# REVERSE_PROTECTION.net
KiCad netlist of a schematic drawn in Altium Designer
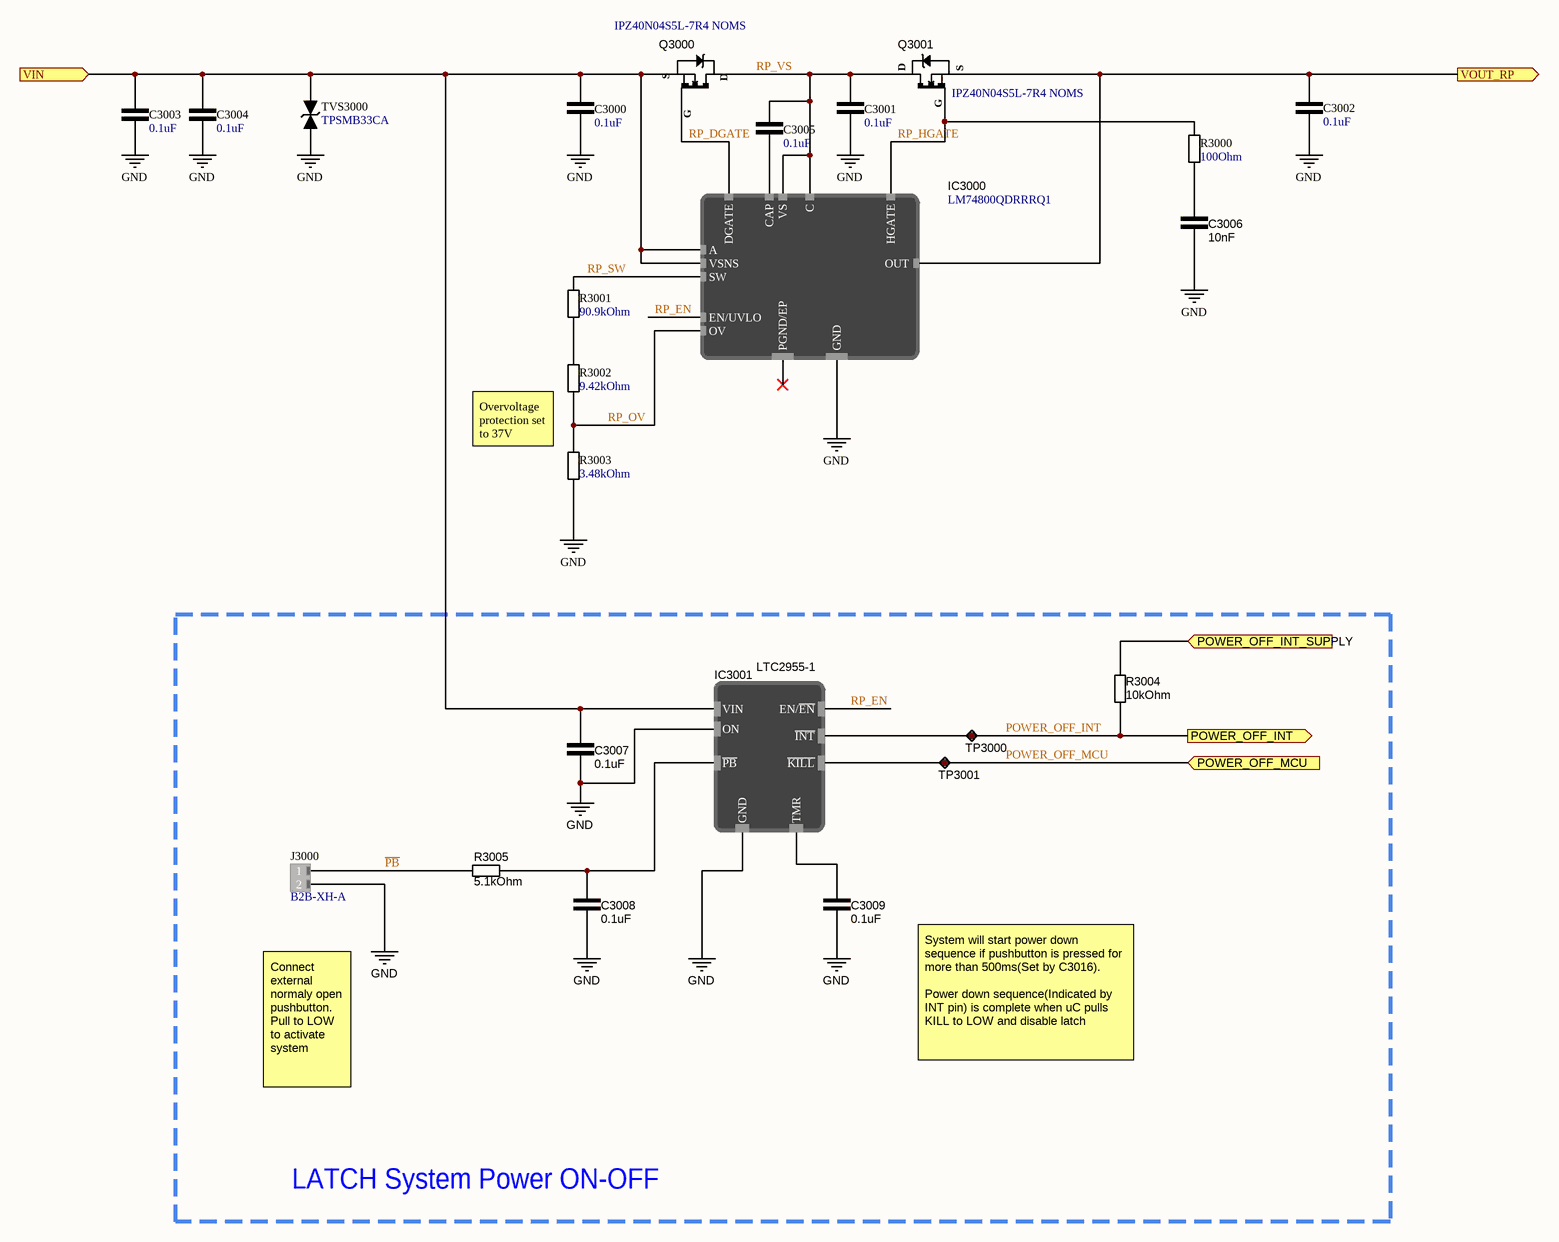
[diagram p0: REVERSE_PROTECTION.SchDoc]

(export (version "E")
  (design (tool "Eeschema 10.0.6"))
  (components
    (comp (ref "C3000")
      (value "0.1uF")
      (footprint "CAP_0603")
      (description "0.1 µF ±10% 50V Ceramic Capacitor X7R 0603 (1608 Metric)")
      (fields (field (name "DIGIKEY PART NUMBER") "1276-1000-1-ND"))
      (libsource (lib "CapacitorsIntegrated") (part "C000018"))
    )
    (comp (ref "C3001")
      (value "0.1uF")
      (footprint "CAP_0603")
      (description "0.1 µF ±10% 50V Ceramic Capacitor X7R 0603 (1608 Metric)")
      (fields (field (name "DIGIKEY PART NUMBER") "1276-1000-1-ND"))
      (libsource (lib "CapacitorsIntegrated") (part "C000018"))
    )
    (comp (ref "C3002")
      (value "0.1uF")
      (footprint "CAP_0603")
      (description "0.1 µF ±10% 50V Ceramic Capacitor X7R 0603 (1608 Metric)")
      (fields (field (name "DIGIKEY PART NUMBER") "1276-1000-1-ND"))
      (libsource (lib "CapacitorsIntegrated") (part "C000018"))
    )
    (comp (ref "C3003")
      (value "0.1uF")
      (footprint "CAP_0603")
      (description "0.1 µF ±10% 50V Ceramic Capacitor X7R 0603 (1608 Metric)")
      (fields (field (name "DIGIKEY PART NUMBER") "1276-1000-1-ND"))
      (libsource (lib "CapacitorsIntegrated") (part "C000018"))
    )
    (comp (ref "C3004")
      (value "0.1uF")
      (footprint "CAP_0603")
      (description "0.1 µF ±10% 50V Ceramic Capacitor X7R 0603 (1608 Metric)")
      (fields (field (name "DIGIKEY PART NUMBER") "1276-1000-1-ND"))
      (libsource (lib "CapacitorsIntegrated") (part "C000018"))
    )
    (comp (ref "C3005")
      (value "0.1uF")
      (footprint "CAP_0603")
      (description "0.1 µF ±10% 50V Ceramic Capacitor X7R 0603 (1608 Metric)")
      (fields (field (name "DIGIKEY PART NUMBER") "1276-1000-1-ND"))
      (libsource (lib "CapacitorsIntegrated") (part "C000018"))
    )
    (comp (ref "C3006")
      (value "10nF")
      (footprint "CAP_0603")
      (description "10000 pF ±10% 50V Ceramic Capacitor X7R 0603 (1608 Metric)")
      (fields (field (name "DIGIKEY PART NUMBER") "399-C0603C103K5RACTUCT-ND"))
      (libsource (lib "CapacitorsIntegrated") (part "C000034"))
    )
    (comp (ref "C3007")
      (value "0.1uF")
      (footprint "CAP_0603")
      (description "0.1 µF ±10% 50V Ceramic Capacitor X7R 0603 (1608 Metric)")
      (fields (field (name "DIGIKEY PART NUMBER") "1276-1000-1-ND"))
      (libsource (lib "CapacitorsIntegrated") (part "C000018"))
    )
    (comp (ref "C3008")
      (value "0.1uF")
      (footprint "CAP_0603")
      (description "0.1 µF ±10% 50V Ceramic Capacitor X7R 0603 (1608 Metric)")
      (fields (field (name "DIGIKEY PART NUMBER") "1276-1000-1-ND"))
      (libsource (lib "CapacitorsIntegrated") (part "C000018"))
    )
    (comp (ref "C3009")
      (value "0.1uF")
      (footprint "CAP_0603")
      (description "0.1 µF ±10% 50V Ceramic Capacitor X7R 0603 (1608 Metric)")
      (fields (field (name "DIGIKEY PART NUMBER") "1276-1000-1-ND"))
      (libsource (lib "CapacitorsIntegrated") (part "C000018"))
    )
    (comp (ref "IC3000")
      (value "LM74800QDRRRQ1")
      (footprint "SON50P300X80_HS-13N")
      (description "OR Controller N+1 ORing Controller N-Channel 1:1 12-WSON (3x3)")
      (fields
        (field (name "DIGIKEY PART NUMBER") "296-LM74800QDRRRQ1CT-ND")
        (field (name "MOUSER PART NUMBER") "595-LM74800QDRRRQ1")
      )
      (libsource (lib "IntegratedCircuits") (part "LM74800QDRRRQ1"))
    )
    (comp (ref "IC3001")
      (value "LTC2955-1")
      (footprint "TSOP65P280X100-8N")
      (description "Power Supply Controller Push Button, On/Off Controller TSOT-23-8")
      (fields
        (field (name "DIGIKEY PART NUMBER") "505-LTC2955CTS8-1#TRMPBFCT-ND")
        (field (name "MOUSER PART NUMBER") "584-C2955CTS8-1TMPF")
      )
      (libsource (lib "IntegratedCircuits") (part "LTC2955-1"))
    )
    (comp (ref "J3000")
      (value "B2B-XH-A")
      (footprint "JST_XH_2POS")
      (description "Connector Header Through Hole 2 position 0.098\" (2.50mm)")
      (fields (field (name "DIGIKEY PART NUMBER") "455-B2B-XH-A-ND"))
      (libsource (lib "ElectroMechanical") (part "00000013"))
    )
    (comp (ref "Q3000")
      (value "IPZ40N04S5L-7R4 NOMS")
      (footprint "PG-TSDSON-8-32")
      (description "N-Channel 40 V 40A (Tc) 34W (Tc) Surface Mount PG-TSDSON-8")
      (fields
        (field (name "DIGIKEY PART NUMBER") "IPZ40N04S5L7R4ATMA1CT-ND")
        (field (name "MOUSER PART NUMBER") "726-IPZ40N04S5L7R4AT")
      )
      (libsource (lib "") (part "00000007_1"))
    )
    (comp (ref "Q3001")
      (value "IPZ40N04S5L-7R4 NOMS")
      (footprint "PG-TSDSON-8-32")
      (description "N-Channel 40 V 40A (Tc) 34W (Tc) Surface Mount PG-TSDSON-8")
      (fields
        (field (name "DIGIKEY PART NUMBER") "IPZ40N04S5L7R4ATMA1CT-ND")
        (field (name "MOUSER PART NUMBER") "726-IPZ40N04S5L7R4AT")
      )
      (libsource (lib "Miscellaneous_Lib1") (part "00000007"))
    )
    (comp (ref "R3000")
      (value "100Ohm")
      (footprint "RES_0603")
      (description "100 Ohms ±1% 0.1W, 1/10W Chip Resistor 0603 (1608 Metric) Moisture Resistant Thick Film")
      (fields (field (name "DIGIKEY PART NUMBER") "311-100HRCT-ND"))
      (libsource (lib "ResistorsIntegrated") (part "R000030"))
    )
    (comp (ref "R3001")
      (value "90.9kOhm")
      (footprint "RES_0603")
      (description "90.9 kOhms ±1% 0.1W, 1/10W Chip Resistor 0603 (1608 Metric) Automotive AEC-Q200 Thick Film")
      (fields (field (name "DIGIKEY PART NUMBER") "P90.9KHCT-ND"))
      (libsource (lib "ResistorsIntegrated") (part "R000027"))
    )
    (comp (ref "R3002")
      (value "9.42kOhm")
      (footprint "RES_0603")
      (fields (field (name "DIGIKEY PART NUMBER") "2019-RN73H1JTTD9421F25CT-ND"))
      (libsource (lib "ResistorsIntegrated") (part "R000028"))
    )
    (comp (ref "R3003")
      (value "3.48kOhm")
      (footprint "RES_0603")
      (description "3.48 kOhms ±1% 0.1W, 1/10W Chip Resistor 0603 (1608 Metric) Automotive AEC-Q200 Thick Film")
      (fields (field (name "DIGIKEY PART NUMBER") "RMCF0603FT3K48CT-ND"))
      (libsource (lib "ResistorsIntegrated") (part "R000029"))
    )
    (comp (ref "R3004")
      (value "10kOhm")
      (footprint "RES_0603")
      (description "10 kOhms ±1% 0.125W, 1/8W Chip Resistor 0603 (1608 Metric) Anti-Sulfur Thin Film")
      (fields (field (name "DIGIKEY PART NUMBER") "MCT0603-10.0K-CFCT-ND"))
      (libsource (lib "ResistorsIntegrated") (part "R000001"))
    )
    (comp (ref "R3005")
      (value "5.1kOhm")
      (footprint "RES_0603")
      (description "5.1 kOhms ±1% 0.1W, 1/10W Chip Resistor 0603 (1608 Metric) Moisture Resistant Thick Film")
      (fields (field (name "DIGIKEY PART NUMBER") "311-5.10KHRCT-ND"))
      (libsource (lib "ResistorsIntegrated") (part "R000013"))
    )
    (comp (ref "TP3000")
      (value "Test point")
      (footprint "TestPoint")
      (description "Test point 1mm")
      (libsource (lib "IntegratedCircuits") (part "TP002"))
    )
    (comp (ref "TP3001")
      (value "Test point")
      (footprint "TestPoint")
      (description "Test point 1mm")
      (libsource (lib "IntegratedCircuits") (part "TP002"))
    )
    (comp (ref "TVS3000")
      (value "TPSMB33CA")
      (footprint "DO-214AA")
      (description "45.7V Clamp 13.3A Ipp Tvs Diode Surface Mount DO-214AA (SMBJ)")
      (fields (field (name "DIGIKEY PART NUMBER") "F6323CT-ND") (field (name "JLCPCB PART NUMBER") "C224085"))
      (libsource (lib "Miscellaneous_Lib1") (part "00000015"))
    )
  )
  (nets
    (net (code "1") (name "/POWER_OFF_INT") (class "Default")
      (node (ref "IC3001") (pin "8") (pinfunction "~{INT}_8") (pintype "passive"))
      (node (ref "R3004") (pin "1") (pinfunction "1_1") (pintype "passive"))
      (node (ref "TP3000") (pin "1") (pinfunction "1_1") (pintype "passive"))
    )
    (net (code "2") (name "/POWER_OFF_INT_SUPPLY") (class "Default")
      (node (ref "R3004") (pin "2") (pinfunction "2_2") (pintype "passive"))
    )
    (net (code "3") (name "/POWER_OFF_MCU") (class "Default")
      (node (ref "IC3001") (pin "2") (pinfunction "~{KILL}_2") (pintype "passive"))
      (node (ref "TP3001") (pin "1") (pinfunction "1_1") (pintype "passive"))
    )
    (net (code "4") (name "/RP_DGATE") (class "Default")
      (node (ref "IC3000") (pin "1") (pinfunction "DGATE_1") (pintype "passive"))
      (node (ref "Q3000") (pin "G") (pinfunction "Gate_G") (pintype "passive"))
    )
    (net (code "5") (name "/RP_EN") (class "Default")
      (node (ref "IC3000") (pin "6") (pinfunction "EN/UVLO_6") (pintype "passive"))
      (node (ref "IC3001") (pin "7") (pinfunction "EN/~{EN}_7") (pintype "open_collector"))
    )
    (net (code "6") (name "/RP_HGATE") (class "Default")
      (node (ref "IC3000") (pin "8") (pinfunction "HGATE_8") (pintype "passive"))
      (node (ref "Q3001") (pin "G") (pinfunction "Gate_G") (pintype "passive"))
      (node (ref "R3000") (pin "2") (pinfunction "2_2") (pintype "passive"))
    )
    (net (code "7") (name "/RP_OV") (class "Default")
      (node (ref "IC3000") (pin "5") (pinfunction "OV_5") (pintype "passive"))
      (node (ref "R3002") (pin "1") (pinfunction "1_1") (pintype "passive"))
      (node (ref "R3003") (pin "2") (pinfunction "2_2") (pintype "passive"))
    )
    (net (code "8") (name "/RP_SW") (class "Default")
      (node (ref "IC3000") (pin "4") (pinfunction "SW_4") (pintype "passive"))
      (node (ref "R3001") (pin "2") (pinfunction "2_2") (pintype "passive"))
    )
    (net (code "9") (name "/RP_VS") (class "Default")
      (node (ref "C3001") (pin "2") (pinfunction "2_2") (pintype "passive"))
      (node (ref "C3005") (pin "2") (pinfunction "2_2") (pintype "passive"))
      (node (ref "IC3000") (pin "10") (pinfunction "VS_10") (pintype "passive"))
      (node (ref "IC3000") (pin "12") (pinfunction "C_12") (pintype "passive"))
      (node (ref "Q3000") (pin "D") (pinfunction "Drain_D") (pintype "passive"))
      (node (ref "Q3001") (pin "D") (pinfunction "Drain_D") (pintype "passive"))
    )
    (net (code "10") (name "/VIN") (class "Default")
      (node (ref "C3000") (pin "2") (pinfunction "2_2") (pintype "passive"))
      (node (ref "C3003") (pin "2") (pinfunction "2_2") (pintype "passive"))
      (node (ref "C3004") (pin "2") (pinfunction "2_2") (pintype "passive"))
      (node (ref "C3007") (pin "2") (pinfunction "2_2") (pintype "passive"))
      (node (ref "IC3000") (pin "2") (pinfunction "A_2") (pintype "passive"))
      (node (ref "IC3000") (pin "3") (pinfunction "VSNS_3") (pintype "passive"))
      (node (ref "IC3001") (pin "6") (pinfunction "VIN_6") (pintype "passive"))
      (node (ref "Q3000") (pin "S") (pinfunction "Source_S") (pintype "passive"))
      (node (ref "TVS3000") (pin "1") (pinfunction "Cathode_1") (pintype "passive"))
    )
    (net (code "11") (name "/VOUT_RP") (class "Default")
      (node (ref "C3002") (pin "2") (pinfunction "2_2") (pintype "passive"))
      (node (ref "IC3000") (pin "9") (pinfunction "OUT_9") (pintype "passive"))
      (node (ref "Q3001") (pin "S") (pinfunction "Source_S") (pintype "passive"))
    )
    (net (code "12") (name "/~{PB}") (class "Default")
      (node (ref "J3000") (pin "1") (pinfunction "1_1") (pintype "passive"))
      (node (ref "R3005") (pin "1") (pinfunction "1_1") (pintype "passive"))
    )
    (net (code "13") (name "GND") (class "Default")
      (node (ref "C3000") (pin "1") (pinfunction "1_1") (pintype "passive"))
      (node (ref "C3001") (pin "1") (pinfunction "1_1") (pintype "passive"))
      (node (ref "C3002") (pin "1") (pinfunction "1_1") (pintype "passive"))
      (node (ref "C3003") (pin "1") (pinfunction "1_1") (pintype "passive"))
      (node (ref "C3004") (pin "1") (pinfunction "1_1") (pintype "passive"))
      (node (ref "C3006") (pin "1") (pinfunction "1_1") (pintype "passive"))
      (node (ref "C3007") (pin "1") (pinfunction "1_1") (pintype "passive"))
      (node (ref "C3008") (pin "1") (pinfunction "1_1") (pintype "passive"))
      (node (ref "C3009") (pin "1") (pinfunction "1_1") (pintype "passive"))
      (node (ref "IC3000") (pin "7") (pinfunction "GND_7") (pintype "passive"))
      (node (ref "IC3001") (pin "1") (pinfunction "ON_1") (pintype "passive"))
      (node (ref "IC3001") (pin "4") (pinfunction "GND_4") (pintype "power_in"))
      (node (ref "J3000") (pin "2") (pinfunction "2_2") (pintype "passive"))
      (node (ref "R3003") (pin "1") (pinfunction "1_1") (pintype "passive"))
      (node (ref "TVS3000") (pin "2") (pinfunction "Anode_2") (pintype "passive"))
    )
    (net (code "14") (name "Net-(C3006-Pad2)") (class "Default")
      (node (ref "C3006") (pin "2") (pinfunction "2_2") (pintype "passive"))
      (node (ref "R3000") (pin "1") (pinfunction "1_1") (pintype "passive"))
    )
    (net (code "15") (name "Net-(IC3000-CAP)") (class "Default")
      (node (ref "C3005") (pin "1") (pinfunction "1_1") (pintype "passive"))
      (node (ref "IC3000") (pin "11") (pinfunction "CAP_11") (pintype "passive"))
    )
    (net (code "16") (name "Net-(IC3001-TMR)") (class "Default")
      (node (ref "C3009") (pin "2") (pinfunction "2_2") (pintype "passive"))
      (node (ref "IC3001") (pin "3") (pinfunction "TMR_3") (pintype "passive"))
    )
    (net (code "17") (name "Net-(IC3001-~{PB})") (class "Default")
      (node (ref "C3008") (pin "2") (pinfunction "2_2") (pintype "passive"))
      (node (ref "IC3001") (pin "5") (pinfunction "~{PB}_5") (pintype "passive"))
      (node (ref "R3005") (pin "2") (pinfunction "2_2") (pintype "passive"))
    )
    (net (code "18") (name "Net-(R3001-Pad1)") (class "Default")
      (node (ref "R3001") (pin "1") (pinfunction "1_1") (pintype "passive"))
      (node (ref "R3002") (pin "2") (pinfunction "2_2") (pintype "passive"))
    )
    (net (code "19") (name "unconnected-(IC3000-PGND{slash}EP-Pad13)") (class "Default")
      (node (ref "IC3000") (pin "13") (pinfunction "PGND/EP_13") (pintype "passive+no_connect"))
    )
  )
)
